# bme590_milestone04.net
KiCad netlist of a schematic drawn in EAGLE
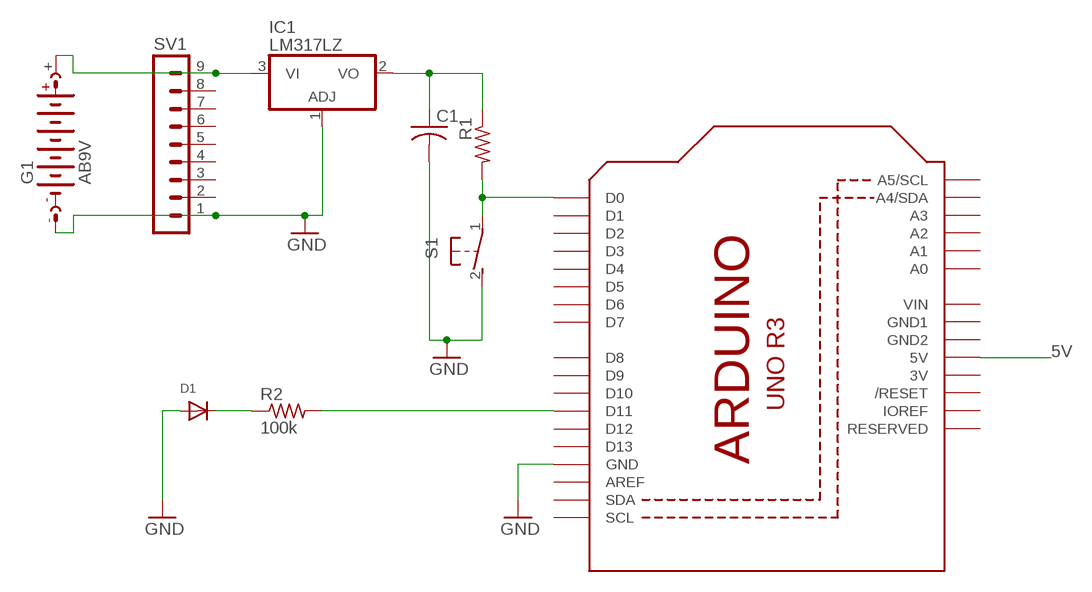
[diagram p0: schematic, sheet 1]

(export (version "E")
  (design (tool "Eeschema 10.0.6"))
  (components
    (comp (ref "C1")
      (value "C-USC0805")
      (footprint "eagle-import:C0805")
      (libsource (lib "eagle-import") (part "C-USC0805"))
    )
    (comp (ref "D1")
      (value "DIODEDO-1N4148")
      (footprint "eagle-import:DO-1N4148")
      (libsource (lib "eagle-import") (part "DIODEDO-1N4148"))
    )
    (comp (ref "G1")
      (value "AB9V")
      (footprint "eagle-import:AB9V")
      (libsource (lib "eagle-import") (part "AB9V"))
    )
    (comp (ref "IC1")
      (value "LM317LZ")
      (footprint "eagle-import:TO92")
      (libsource (lib "eagle-import") (part "317LZLM"))
    )
    (comp (ref "R1")
      (value "R-US_M0805")
      (footprint "eagle-import:M0805")
      (libsource (lib "eagle-import") (part "R-US_M0805"))
    )
    (comp (ref "R2")
      (value "100k")
      (footprint "eagle-import:R0805")
      (libsource (lib "eagle-import") (part "R-US_R0805"))
    )
    (comp (ref "S1")
      (value "31-XX")
      (footprint "eagle-import:B3F-31XX")
      (libsource (lib "eagle-import") (part "31-XX"))
    )
    (comp (ref "SV1")
      (value "MA09-1W")
      (footprint "eagle-import:MA09-1W")
      (libsource (lib "eagle-import") (part "MA09-1W"))
    )
    (comp (ref "U1")
      (value "ARDUINOR3-DIMENSION")
      (footprint "eagle-import:ARDUINOR3")
      (libsource (lib "eagle-import") (part "ARDUINOR3-DIMENSION"))
    )
  )
  (nets
    (net (code "1") (name "/3V") (class "Default")
      (node (ref "U1") (pin "3V") (pinfunction "3V_3V") (pintype "power_in"))
    )
    (net (code "2") (name "/5V") (class "Default")
      (node (ref "U1") (pin "5V") (pinfunction "5V_5V") (pintype "power_in"))
    )
    (net (code "3") (name "/GND1") (class "Default")
      (node (ref "U1") (pin "GND1") (pinfunction "GND1_GND1") (pintype "power_in"))
    )
    (net (code "4") (name "/GND2") (class "Default")
      (node (ref "U1") (pin "GND2") (pinfunction "GND2_GND2") (pintype "power_in"))
    )
    (net (code "5") (name "/VIN") (class "Default")
      (node (ref "U1") (pin "VIN") (pinfunction "VIN_VIN") (pintype "power_in"))
    )
    (net (code "6") (name "GND") (class "Default")
      (node (ref "C1") (pin "2") (pinfunction "2_2") (pintype "passive"))
      (node (ref "D1") (pin "A") (pinfunction "A_A") (pintype "passive"))
      (node (ref "G1") (pin "-") (pinfunction "-_-") (pintype "passive"))
      (node (ref "IC1") (pin "1") (pinfunction "ADJ_1") (pintype "input"))
      (node (ref "S1") (pin "2") (pinfunction "S_2") (pintype "passive"))
      (node (ref "SV1") (pin "1") (pinfunction "1_1") (pintype "passive"))
      (node (ref "U1") (pin "GND") (pinfunction "GND_GND") (pintype "power_in"))
    )
    (net (code "7") (name "Net-(D1-PadC)") (class "Default")
      (node (ref "D1") (pin "C") (pinfunction "C_C") (pintype "passive"))
      (node (ref "R2") (pin "1") (pinfunction "1_1") (pintype "passive"))
    )
    (net (code "8") (name "Net-(IC1-VI)") (class "Default")
      (node (ref "G1") (pin "+") (pinfunction "+_+") (pintype "passive"))
      (node (ref "IC1") (pin "3") (pinfunction "VI_3") (pintype "input"))
      (node (ref "SV1") (pin "9") (pinfunction "9_9") (pintype "passive"))
    )
    (net (code "9") (name "Net-(IC1-VO)") (class "Default")
      (node (ref "C1") (pin "1") (pinfunction "1_1") (pintype "passive"))
      (node (ref "IC1") (pin "2") (pinfunction "VO_2") (pintype "passive"))
      (node (ref "R1") (pin "1") (pinfunction "1_1") (pintype "passive"))
    )
    (net (code "10") (name "Net-(R2-Pad2)") (class "Default")
      (node (ref "R2") (pin "2") (pinfunction "2_2") (pintype "passive"))
      (node (ref "U1") (pin "D11") (pinfunction "D11_D11") (pintype "bidirectional"))
    )
    (net (code "11") (name "Net-(S1-P)") (class "Default")
      (node (ref "R1") (pin "2") (pinfunction "2_2") (pintype "passive"))
      (node (ref "S1") (pin "1") (pinfunction "P_1") (pintype "passive"))
      (node (ref "U1") (pin "D0") (pinfunction "D0_D0") (pintype "bidirectional"))
    )
    (net (code "12") (name "unconnected-(SV1-Pad2)") (class "Default")
      (node (ref "SV1") (pin "2") (pinfunction "2_2") (pintype "passive"))
    )
    (net (code "13") (name "unconnected-(SV1-Pad3)") (class "Default")
      (node (ref "SV1") (pin "3") (pinfunction "3_3") (pintype "passive"))
    )
    (net (code "14") (name "unconnected-(SV1-Pad4)") (class "Default")
      (node (ref "SV1") (pin "4") (pinfunction "4_4") (pintype "passive"))
    )
    (net (code "15") (name "unconnected-(SV1-Pad5)") (class "Default")
      (node (ref "SV1") (pin "5") (pinfunction "5_5") (pintype "passive"))
    )
    (net (code "16") (name "unconnected-(SV1-Pad6)") (class "Default")
      (node (ref "SV1") (pin "6") (pinfunction "6_6") (pintype "passive"))
    )
    (net (code "17") (name "unconnected-(SV1-Pad7)") (class "Default")
      (node (ref "SV1") (pin "7") (pinfunction "7_7") (pintype "passive"))
    )
    (net (code "18") (name "unconnected-(SV1-Pad8)") (class "Default")
      (node (ref "SV1") (pin "8") (pinfunction "8_8") (pintype "passive"))
    )
    (net (code "19") (name "unconnected-(U1-A4{slash}SDA-PadA4)") (class "Default")
      (node (ref "U1") (pin "A4") (pinfunction "A4/SDA_A4") (pintype "bidirectional"))
    )
    (net (code "20") (name "unconnected-(U1-A5{slash}SCL-PadA5)") (class "Default")
      (node (ref "U1") (pin "A5") (pinfunction "A5/SCL_A5") (pintype "bidirectional"))
    )
    (net (code "21") (name "unconnected-(U1-PadA0)") (class "Default")
      (node (ref "U1") (pin "A0") (pinfunction "A0_A0") (pintype "bidirectional"))
    )
    (net (code "22") (name "unconnected-(U1-PadA1)") (class "Default")
      (node (ref "U1") (pin "A1") (pinfunction "A1_A1") (pintype "bidirectional"))
    )
    (net (code "23") (name "unconnected-(U1-PadA2)") (class "Default")
      (node (ref "U1") (pin "A2") (pinfunction "A2_A2") (pintype "bidirectional"))
    )
    (net (code "24") (name "unconnected-(U1-PadA3)") (class "Default")
      (node (ref "U1") (pin "A3") (pinfunction "A3_A3") (pintype "bidirectional"))
    )
    (net (code "25") (name "unconnected-(U1-PadAREF)") (class "Default")
      (node (ref "U1") (pin "AREF") (pinfunction "AREF_AREF") (pintype "bidirectional"))
    )
    (net (code "26") (name "unconnected-(U1-PadD1)") (class "Default")
      (node (ref "U1") (pin "D1") (pinfunction "D1_D1") (pintype "bidirectional"))
    )
    (net (code "27") (name "unconnected-(U1-PadD2)") (class "Default")
      (node (ref "U1") (pin "D2") (pinfunction "D2_D2") (pintype "bidirectional"))
    )
    (net (code "28") (name "unconnected-(U1-PadD3)") (class "Default")
      (node (ref "U1") (pin "D3") (pinfunction "D3_D3") (pintype "bidirectional"))
    )
    (net (code "29") (name "unconnected-(U1-PadD4)") (class "Default")
      (node (ref "U1") (pin "D4") (pinfunction "D4_D4") (pintype "bidirectional"))
    )
    (net (code "30") (name "unconnected-(U1-PadD5)") (class "Default")
      (node (ref "U1") (pin "D5") (pinfunction "D5_D5") (pintype "bidirectional"))
    )
    (net (code "31") (name "unconnected-(U1-PadD6)") (class "Default")
      (node (ref "U1") (pin "D6") (pinfunction "D6_D6") (pintype "bidirectional"))
    )
    (net (code "32") (name "unconnected-(U1-PadD7)") (class "Default")
      (node (ref "U1") (pin "D7") (pinfunction "D7_D7") (pintype "bidirectional"))
    )
    (net (code "33") (name "unconnected-(U1-PadD8)") (class "Default")
      (node (ref "U1") (pin "D8") (pinfunction "D8_D8") (pintype "bidirectional"))
    )
    (net (code "34") (name "unconnected-(U1-PadD9)") (class "Default")
      (node (ref "U1") (pin "D9") (pinfunction "D9_D9") (pintype "bidirectional"))
    )
    (net (code "35") (name "unconnected-(U1-PadD10)") (class "Default")
      (node (ref "U1") (pin "D10") (pinfunction "D10_D10") (pintype "bidirectional"))
    )
    (net (code "36") (name "unconnected-(U1-PadD12)") (class "Default")
      (node (ref "U1") (pin "D12") (pinfunction "D12_D12") (pintype "bidirectional"))
    )
    (net (code "37") (name "unconnected-(U1-PadD13)") (class "Default")
      (node (ref "U1") (pin "D13") (pinfunction "D13_D13") (pintype "bidirectional"))
    )
    (net (code "38") (name "unconnected-(U1-PadIOREF)") (class "Default")
      (node (ref "U1") (pin "IOREF") (pinfunction "IOREF_IOREF") (pintype "output"))
    )
    (net (code "39") (name "unconnected-(U1-PadRESERVED)") (class "Default")
      (node (ref "U1") (pin "RESERVED") (pinfunction "RESERVED_RESERVED") (pintype "no_connect"))
    )
    (net (code "40") (name "unconnected-(U1-PadSCL)") (class "Default")
      (node (ref "U1") (pin "SCL") (pinfunction "SCL_SCL") (pintype "bidirectional"))
    )
    (net (code "41") (name "unconnected-(U1-PadSDA)") (class "Default")
      (node (ref "U1") (pin "SDA") (pinfunction "SDA_SDA") (pintype "bidirectional"))
    )
    (net (code "42") (name "unconnected-(U1-{slash}RESET-PadRESET)") (class "Default")
      (node (ref "U1") (pin "RESET") (pinfunction "/RESET_RESET") (pintype "bidirectional"))
    )
  )
)
